# PWM_PART.net
KiCad netlist of a schematic drawn in Altium Designer
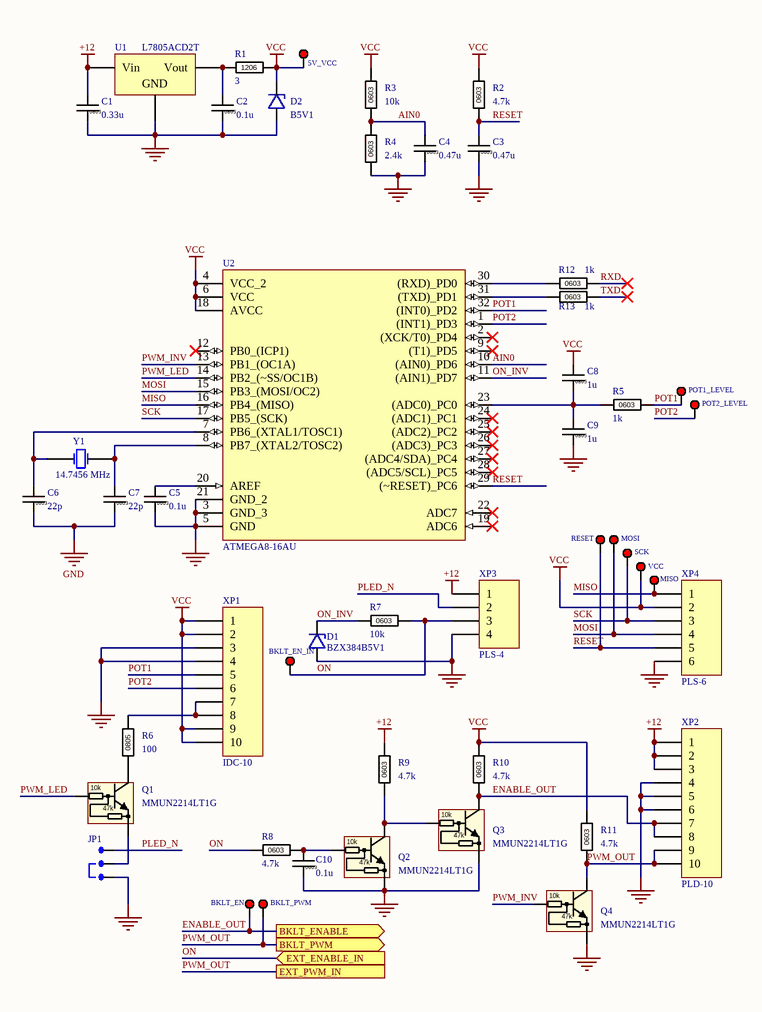
[diagram p0: PWM_PART.SchDoc]

(export (version "E")
  (design (tool "Eeschema 10.0.6"))
  (components
    (comp (ref "C1")
      (value "0805-X7R-100-0.33 мкф K")
      (footprint "CAP_0805")
      (description "Конденсатор Чип Керамический")
      (fields (field (name "VOLTAGE") "100V") (field (name "CAP") "0.33u") (field (name "FOOT") "0805"))
      (libsource (lib "main") (part "0805-X7R-100-0.33 мкф K"))
    )
    (comp (ref "C2")
      (value "0805-X7R-50-0.1 мкф K Hitano")
      (footprint "CAP_0805")
      (description "Конденсатор Чип Керамический")
      (fields (field (name "VOLTAGE") "50V") (field (name "CAP") "0.1u") (field (name "FOOT") "0805"))
      (libsource (lib "main") (part "0805-X7R-50-0.1 мкф K"))
    )
    (comp (ref "C3")
      (value "0603-X7R-50-0.47 мкф")
      (footprint "CAP_0603")
      (description "Конденсатор Чип Керамический")
      (fields (field (name "VOLTAGE") "50V") (field (name "CAP") "0.47u") (field (name "FOOT") "0603"))
      (libsource (lib "main") (part "0603-X7R-50-0.47 мкф"))
    )
    (comp (ref "C4")
      (value "0603-X7R-50-0.47 мкф")
      (footprint "CAP_0603")
      (description "Конденсатор Чип Керамический")
      (fields (field (name "VOLTAGE") "50V") (field (name "CAP") "0.47u") (field (name "FOOT") "0603"))
      (libsource (lib "main") (part "0603-X7R-50-0.47 мкф"))
    )
    (comp (ref "C5")
      (value "0603-X7R-50-0.1 мкф")
      (footprint "CAP_0603")
      (description "Конденсатор Чип Керамический")
      (fields (field (name "VOLTAGE") "50V") (field (name "CAP") "0.1u") (field (name "FOOT") "0603"))
      (libsource (lib "main") (part "0603-X7R-50-0.1 мкф"))
    )
    (comp (ref "C6")
      (value "0603-NP0-50-22 пф F")
      (footprint "CAP_0603")
      (description "Конденсатор Чип Керамический")
      (fields
        (field (name "VOLTAGE") "50V")
        (field (name "TOLERANCE") "1%")
        (field (name "CAP") "22p")
        (field (name "FOOT") "0603")
      )
      (libsource (lib "main") (part "0603-NP0-50-22 пф F"))
    )
    (comp (ref "C7")
      (value "0603-NP0-50-22 пф F")
      (footprint "CAP_0603")
      (description "Конденсатор Чип Керамический")
      (fields
        (field (name "VOLTAGE") "50V")
        (field (name "TOLERANCE") "1%")
        (field (name "CAP") "22p")
        (field (name "FOOT") "0603")
      )
      (libsource (lib "main") (part "0603-NP0-50-22 пф F"))
    )
    (comp (ref "C8")
      (value "0805-X7R-50-1 мкф")
      (footprint "CAP_0805")
      (description "Конденсатор Чип Керамический")
      (fields (field (name "VOLTAGE") "50V") (field (name "CAP") "1u") (field (name "FOOT") "0805"))
      (libsource (lib "main") (part "0805-X7R-50-1 мкф"))
    )
    (comp (ref "C9")
      (value "0805-X7R-50-1 мкф")
      (footprint "CAP_0805")
      (description "Конденсатор Чип Керамический")
      (fields (field (name "VOLTAGE") "50V") (field (name "CAP") "1u") (field (name "FOOT") "0805"))
      (libsource (lib "main") (part "0805-X7R-50-1 мкф"))
    )
    (comp (ref "C10")
      (value "0603-X7R-50-0.1 мкф")
      (footprint "CAP_0603")
      (description "Конденсатор Чип Керамический")
      (fields (field (name "VOLTAGE") "50V") (field (name "CAP") "0.1u") (field (name "FOOT") "0603"))
      (libsource (lib "main") (part "0603-X7R-50-0.1 мкф"))
    )
    (comp (ref "D1")
      (value "BZX384B5V1")
      (footprint "SOD_323 (SC-76)")
      (fields
        (field (name "HELPURL") "L:\\Dev\\Техническая документация\\Стабилитроны\\BZX384_series_Vishay.pdf")
      )
      (libsource (lib "main") (part "BZX384B5V1"))
    )
    (comp (ref "D2")
      (value "B5V1")
      (footprint "SOD_323 (SC-76)")
      (fields
        (field (name "Comment") "BZX384B5V1")
        (field (name "HELPURL") "L:\\Dev\\Техническая документация\\Стабилитроны\\BZX384_series_Vishay.pdf")
      )
      (libsource (lib "main") (part "BZX384B5V1"))
    )
    (comp (ref "JP1")
      (value "~")
      (footprint "CONN_JUMPER 3PIN 2.54MM")
      (libsource (lib "main") (part "CONN_JUMPER 2.54 MM"))
    )
    (comp (ref "Q1")
      (value "MMUN2214LT1G")
      (footprint "SOT_23")
      (description "NPN Digital Transistor")
      (fields (field (name "PUBLISHER") "Altium Limited"))
      (libsource (lib "main") (part "MMUN2214LT1G_50V 0.1A 0.25W"))
    )
    (comp (ref "Q2")
      (value "MMUN2214LT1G")
      (footprint "SOT_23")
      (description "NPN Digital Transistor")
      (fields (field (name "PUBLISHER") "Altium Limited"))
      (libsource (lib "main") (part "MMUN2214LT1G_50V 0.1A 0.25W"))
    )
    (comp (ref "Q3")
      (value "MMUN2214LT1G")
      (footprint "SOT_23")
      (description "NPN Digital Transistor")
      (fields (field (name "PUBLISHER") "Altium Limited"))
      (libsource (lib "main") (part "MMUN2214LT1G_50V 0.1A 0.25W"))
    )
    (comp (ref "Q4")
      (value "MMUN2214LT1G")
      (footprint "SOT_23")
      (description "NPN Digital Transistor")
      (fields (field (name "PUBLISHER") "Altium Limited"))
      (libsource (lib "main") (part "MMUN2214LT1G_50V 0.1A 0.25W"))
    )
    (comp (ref "R1")
      (value "3")
      (footprint "resistor_1206")
      (description "Резистор Чип")
      (fields (field (name "POWER") "0.25W") (field (name "FOOT") "1206") (field (name "Comment") "1206-3 J"))
      (libsource (lib "main") (part "1206-3 J"))
    )
    (comp (ref "R2")
      (value "4.7k")
      (footprint "resistor_0603")
      (description "Резистор Чип")
      (fields
        (field (name "POWER") "0.1W")
        (field (name "FOOT") "0603")
        (field (name "Comment") "0603-4.7 к J")
      )
      (libsource (lib "main") (part "0603-4.7 к J"))
    )
    (comp (ref "R3")
      (value "10k")
      (footprint "resistor_0603")
      (description "Резистор Чип")
      (fields
        (field (name "POWER") "0.1W")
        (field (name "FOOT") "0603")
        (field (name "Comment") "0603-10к J")
      )
      (libsource (lib "main") (part "0603-10 к J"))
    )
    (comp (ref "R4")
      (value "2.4k")
      (footprint "resistor_0603")
      (description "Резистор Чип")
      (fields (field (name "POWER") "0.1W") (field (name "TOLERANCE") "1%") (field (name "FOOT") "0603"))
      (libsource (lib "main") (part "0603-2.49 к F"))
    )
    (comp (ref "R5")
      (value "1k")
      (footprint "RESistor_0603")
      (description "Резистор Чип")
      (fields
        (field (name "POWER") "0.1W")
        (field (name "FOOT") "0603")
        (field (name "Comment") "0603-1 к J")
      )
      (libsource (lib "main") (part "0603-1 к J"))
    )
    (comp (ref "R6")
      (value "100")
      (footprint "resistor_0805")
      (description "Резистор Чип")
      (fields
        (field (name "POWER") "0.125W")
        (field (name "FOOT") "0805")
        (field (name "Comment") "0805-100 J")
      )
      (libsource (lib "main") (part "0805-100 J"))
    )
    (comp (ref "R7")
      (value "10k")
      (footprint "resistor_0603")
      (description "Резистор Чип")
      (fields
        (field (name "POWER") "0.1W")
        (field (name "FOOT") "0603")
        (field (name "Comment") "0603-10к J")
      )
      (libsource (lib "main") (part "0603-10 к J"))
    )
    (comp (ref "R8")
      (value "4.7k")
      (footprint "resistor_0603")
      (description "Резистор Чип")
      (fields
        (field (name "POWER") "0.1W")
        (field (name "FOOT") "0603")
        (field (name "Comment") "0603-4.7 к J")
      )
      (libsource (lib "main") (part "0603-4.7 к J"))
    )
    (comp (ref "R9")
      (value "4.7k")
      (footprint "resistor_0603")
      (description "Резистор Чип")
      (fields
        (field (name "POWER") "0.1W")
        (field (name "FOOT") "0603")
        (field (name "Comment") "0603-4.7 к J")
      )
      (libsource (lib "main") (part "0603-4.7 к J"))
    )
    (comp (ref "R10")
      (value "4.7k")
      (footprint "resistor_0603")
      (description "Резистор Чип")
      (fields
        (field (name "POWER") "0.1W")
        (field (name "FOOT") "0603")
        (field (name "Comment") "0603-4.7 к J")
      )
      (libsource (lib "main") (part "0603-4.7 к J"))
    )
    (comp (ref "R11")
      (value "4.7k")
      (footprint "resistor_0603")
      (description "Резистор Чип")
      (fields
        (field (name "POWER") "0.1W")
        (field (name "FOOT") "0603")
        (field (name "Comment") "0603-4.7 к J")
      )
      (libsource (lib "main") (part "0603-4.7 к J"))
    )
    (comp (ref "R12")
      (value "1k")
      (footprint "RESistor_0603")
      (description "Резистор Чип")
      (fields
        (field (name "POWER") "0.1W")
        (field (name "FOOT") "0603")
        (field (name "Comment") "0603-1 к J")
      )
      (libsource (lib "main") (part "0603-1 к J"))
    )
    (comp (ref "R13")
      (value "1k")
      (footprint "RESistor_0603")
      (description "Резистор Чип")
      (fields
        (field (name "POWER") "0.1W")
        (field (name "FOOT") "0603")
        (field (name "Comment") "0603-1 к J")
      )
      (libsource (lib "main") (part "0603-1 к J"))
    )
    (comp (ref "TP1")
      (value "5V_VCC")
      (footprint "OTHER_SMD_TP_1.5MM")
      (libsource (lib "main") (part "Test Point_1.5MM"))
    )
    (comp (ref "TP2")
      (value "MISO")
      (footprint "OTHER_SMD_TP_1.5MM")
      (libsource (lib "main") (part "Test Point_1.5MM"))
    )
    (comp (ref "TP3")
      (value "VCC")
      (footprint "OTHER_SMD_TP_1.5MM")
      (libsource (lib "main") (part "Test Point_1.5MM"))
    )
    (comp (ref "TP4")
      (value "SCK")
      (footprint "OTHER_SMD_TP_1.5MM")
      (libsource (lib "main") (part "Test Point_1.5MM"))
    )
    (comp (ref "TP5")
      (value "MOSI")
      (footprint "OTHER_SMD_TP_1.5MM")
      (libsource (lib "main") (part "Test Point_1.5MM"))
    )
    (comp (ref "TP6")
      (value "RESET")
      (footprint "OTHER_SMD_TP_1.5MM")
      (libsource (lib "main") (part "Test Point_1.5MM"))
    )
    (comp (ref "TP7")
      (value "BKLT_EN")
      (footprint "OTHER_SMD_TP_1.5MM")
      (libsource (lib "main") (part "Test Point_1.5MM"))
    )
    (comp (ref "TP8")
      (value "BKLT_PWM")
      (footprint "OTHER_SMD_TP_1.5MM")
      (libsource (lib "main") (part "Test Point_1.5MM"))
    )
    (comp (ref "TP9")
      (value "BKLT_EN_IN")
      (footprint "OTHER_SMD_TP_1.5MM")
      (libsource (lib "main") (part "Test Point_1.5MM"))
    )
    (comp (ref "TP10")
      (value "POT1_LEVEL")
      (footprint "OTHER_SMD_TP_1.5MM")
      (libsource (lib "main") (part "Test Point_1.5MM"))
    )
    (comp (ref "TP11")
      (value "POT2_LEVEL")
      (footprint "OTHER_SMD_TP_1.5MM")
      (libsource (lib "main") (part "Test Point_1.5MM"))
    )
    (comp (ref "U1")
      (value "L7805ACD2T")
      (footprint "D2-PAK")
      (description "Стабилизатор напряжения +5В 1.5А, [D2-PAK]")
      (fields (field (name "PUBLISHER") "Altium Limited"))
      (libsource (lib "main") (part "LDO_L7805ACD2T-TR"))
    )
    (comp (ref "U2")
      (value "ATMEGA8-16AU")
      (footprint "TQFP_32")
      (description "AVR AVRÂ® ATmega Microcontroller IC 8-Bit 16MHz 8KB _4K x 16_ FLASH 32-TQFP _7x7_")
      (fields (field (name "MF") "Microchip Technology"))
      (libsource (lib "main") (part "MCU_ATMEGA8-16AU"))
    )
    (comp (ref "XP1")
      (value "IDC-10")
      (footprint "CONN_IDC-10")
      (description "Header, 10-Pin")
      (fields (field (name "PUBLISHER") "Altium Limited"))
      (libsource (lib "main") (part "CONN_IDC-10 (Single Row)"))
    )
    (comp (ref "XP2")
      (value "PLD-10")
      (footprint "CONN_PLD-10")
      (description "Header, 10-Pin")
      (fields (field (name "PUBLISHER") "Altium Limited"))
      (libsource (lib "main") (part "CONN_Header 10 (Single Row)_1"))
    )
    (comp (ref "XP3")
      (value "PLS-4")
      (footprint "CONN_PLS-4")
      (description "Header, 4-Pin")
      (fields (field (name "PUBLISHER") "Altium Limited"))
      (libsource (lib "main") (part "CONN_PLS-4"))
    )
    (comp (ref "XP4")
      (value "PLS-6")
      (footprint "CONN_PLD-6")
      (description "Header, 6-Pin")
      (fields (field (name "PUBLISHER") "Altium Limited"))
      (libsource (lib "main") (part "CONN_PLS-6"))
    )
    (comp (ref "Y1")
      (value "14.7456 MHz")
      (footprint "CRYSTAL_HC-49S")
      (description "14.7456 МГц имп. HC-49SM, Кварцевый резонатор")
      (fields (field (name "PUBLISHER") "Altium Limited"))
      (libsource (lib "main") (part "CRYSTAL_14.7456 MHz"))
    )
  )
  (nets
    (net (code "1") (name "+12") (class "Default")
      (node (ref "C1") (pin "1") (pinfunction "1_1") (pintype "passive"))
      (node (ref "R9") (pin "2") (pinfunction "2_2") (pintype "passive"))
      (node (ref "U1") (pin "1") (pinfunction "Vin_1") (pintype "passive"))
      (node (ref "XP2") (pin "1") (pinfunction "1_1") (pintype "passive"))
      (node (ref "XP2") (pin "2") (pinfunction "2_2") (pintype "passive"))
      (node (ref "XP2") (pin "3") (pinfunction "3_3") (pintype "passive"))
      (node (ref "XP3") (pin "1") (pinfunction "1_1") (pintype "passive"))
    )
    (net (code "2") (name "/AIN0") (class "Default")
      (node (ref "C4") (pin "1") (pinfunction "1_1") (pintype "passive"))
      (node (ref "R3") (pin "1") (pinfunction "1_1") (pintype "passive"))
      (node (ref "R4") (pin "2") (pinfunction "2_2") (pintype "passive"))
      (node (ref "U2") (pin "10") (pinfunction "(AIN0)_PD6_10") (pintype "bidirectional"))
    )
    (net (code "3") (name "/ENABLE_OUT") (class "Default")
      (node (ref "Q3") (pin "3") (pinfunction "C_3") (pintype "passive"))
      (node (ref "R10") (pin "1") (pinfunction "1_1") (pintype "passive"))
      (node (ref "TP7") (pin "1") (pinfunction "1_1") (pintype "passive"))
      (node (ref "XP2") (pin "7") (pinfunction "7_7") (pintype "passive"))
      (node (ref "XP2") (pin "8") (pinfunction "8_8") (pintype "passive"))
    )
    (net (code "4") (name "/MISO") (class "Default")
      (node (ref "TP2") (pin "1") (pinfunction "1_1") (pintype "passive"))
      (node (ref "U2") (pin "16") (pinfunction "PB4_(MISO)_16") (pintype "bidirectional"))
      (node (ref "XP4") (pin "1") (pinfunction "1_1") (pintype "passive"))
    )
    (net (code "5") (name "/MOSI") (class "Default")
      (node (ref "TP5") (pin "1") (pinfunction "1_1") (pintype "passive"))
      (node (ref "U2") (pin "15") (pinfunction "PB3_(MOSI/OC2)_15") (pintype "bidirectional"))
      (node (ref "XP4") (pin "4") (pinfunction "4_4") (pintype "passive"))
    )
    (net (code "6") (name "/ON") (class "Default")
      (node (ref "R7") (pin "2") (pinfunction "2_2") (pintype "passive"))
      (node (ref "R8") (pin "1") (pinfunction "1_1") (pintype "passive"))
      (node (ref "TP9") (pin "1") (pinfunction "1_1") (pintype "passive"))
      (node (ref "XP3") (pin "3") (pinfunction "3_3") (pintype "passive"))
    )
    (net (code "7") (name "/ON_INV") (class "Default")
      (node (ref "D1") (pin "C") (pinfunction "2_C") (pintype "passive"))
      (node (ref "R7") (pin "1") (pinfunction "1_1") (pintype "passive"))
      (node (ref "U2") (pin "11") (pinfunction "(AIN1)_PD7_11") (pintype "bidirectional"))
    )
    (net (code "8") (name "/PLED_N") (class "Default")
      (node (ref "JP1") (pin "3") (pinfunction "3_3") (pintype "passive"))
      (node (ref "XP3") (pin "2") (pinfunction "2_2") (pintype "passive"))
    )
    (net (code "9") (name "/POT1") (class "Default")
      (node (ref "R5") (pin "2") (pinfunction "2_2") (pintype "passive"))
      (node (ref "TP10") (pin "1") (pinfunction "1_1") (pintype "passive"))
      (node (ref "U2") (pin "32") (pinfunction "(INT0)_PD2_32") (pintype "bidirectional"))
      (node (ref "XP1") (pin "5") (pinfunction "5_5") (pintype "passive"))
    )
    (net (code "10") (name "/POT2") (class "Default")
      (node (ref "TP11") (pin "1") (pinfunction "1_1") (pintype "passive"))
      (node (ref "U2") (pin "1") (pinfunction "(INT1)_PD3_1") (pintype "bidirectional"))
      (node (ref "XP1") (pin "6") (pinfunction "6_6") (pintype "passive"))
    )
    (net (code "11") (name "/PWM_INV") (class "Default")
      (node (ref "Q4") (pin "1") (pinfunction "B_1") (pintype "passive"))
      (node (ref "U2") (pin "13") (pinfunction "PB1_(OC1A)_13") (pintype "bidirectional"))
    )
    (net (code "12") (name "/PWM_LED") (class "Default")
      (node (ref "Q1") (pin "1") (pinfunction "B_1") (pintype "passive"))
      (node (ref "U2") (pin "14") (pinfunction "PB2_(~SS/OC1B)_14") (pintype "bidirectional"))
    )
    (net (code "13") (name "/PWM_OUT") (class "Default")
      (node (ref "Q4") (pin "3") (pinfunction "C_3") (pintype "passive"))
      (node (ref "R11") (pin "1") (pinfunction "1_1") (pintype "passive"))
      (node (ref "TP8") (pin "1") (pinfunction "1_1") (pintype "passive"))
      (node (ref "XP2") (pin "10") (pinfunction "10_10") (pintype "passive"))
      (node (ref "XP2") (pin "9") (pinfunction "9_9") (pintype "passive"))
    )
    (net (code "14") (name "/RESET") (class "Default")
      (node (ref "C3") (pin "1") (pinfunction "1_1") (pintype "passive"))
      (node (ref "R2") (pin "1") (pinfunction "1_1") (pintype "passive"))
      (node (ref "TP6") (pin "1") (pinfunction "1_1") (pintype "passive"))
      (node (ref "U2") (pin "29") (pinfunction "(~RESET)_PC6_29") (pintype "bidirectional"))
      (node (ref "XP4") (pin "5") (pinfunction "5_5") (pintype "passive"))
    )
    (net (code "15") (name "/RXD") (class "Default")
      (node (ref "R12") (pin "2") (pinfunction "2_2") (pintype "passive+no_connect"))
    )
    (net (code "16") (name "/SCK") (class "Default")
      (node (ref "TP4") (pin "1") (pinfunction "1_1") (pintype "passive"))
      (node (ref "U2") (pin "17") (pinfunction "PB5_(SCK)_17") (pintype "bidirectional"))
      (node (ref "XP4") (pin "3") (pinfunction "3_3") (pintype "passive"))
    )
    (net (code "17") (name "/TXD") (class "Default")
      (node (ref "R13") (pin "2") (pinfunction "2_2") (pintype "passive+no_connect"))
    )
    (net (code "18") (name "GND") (class "Default")
      (node (ref "C1") (pin "2") (pinfunction "2_2") (pintype "passive"))
      (node (ref "C10") (pin "2") (pinfunction "2_2") (pintype "passive"))
      (node (ref "C2") (pin "2") (pinfunction "2_2") (pintype "passive"))
      (node (ref "C3") (pin "2") (pinfunction "2_2") (pintype "passive"))
      (node (ref "C4") (pin "2") (pinfunction "2_2") (pintype "passive"))
      (node (ref "C5") (pin "2") (pinfunction "2_2") (pintype "passive"))
      (node (ref "C6") (pin "2") (pinfunction "2_2") (pintype "passive"))
      (node (ref "C7") (pin "2") (pinfunction "2_2") (pintype "passive"))
      (node (ref "C9") (pin "2") (pinfunction "2_2") (pintype "passive"))
      (node (ref "D1") (pin "A") (pinfunction "1_A") (pintype "passive"))
      (node (ref "D2") (pin "A") (pinfunction "1_A") (pintype "passive"))
      (node (ref "JP1") (pin "1") (pinfunction "1_1") (pintype "passive"))
      (node (ref "Q2") (pin "2") (pinfunction "E_2") (pintype "passive"))
      (node (ref "Q3") (pin "2") (pinfunction "E_2") (pintype "passive"))
      (node (ref "Q4") (pin "2") (pinfunction "E_2") (pintype "passive"))
      (node (ref "R4") (pin "1") (pinfunction "1_1") (pintype "passive"))
      (node (ref "U1") (pin "2") (pinfunction "GND_2") (pintype "passive"))
      (node (ref "U2") (pin "21") (pinfunction "GND_2_21") (pintype "passive"))
      (node (ref "U2") (pin "3") (pinfunction "GND_3_3") (pintype "passive"))
      (node (ref "U2") (pin "5") (pinfunction "GND_5") (pintype "passive"))
      (node (ref "XP1") (pin "3") (pinfunction "3_3") (pintype "passive"))
      (node (ref "XP1") (pin "4") (pinfunction "4_4") (pintype "passive"))
      (node (ref "XP2") (pin "4") (pinfunction "4_4") (pintype "passive"))
      (node (ref "XP2") (pin "5") (pinfunction "5_5") (pintype "passive"))
      (node (ref "XP2") (pin "6") (pinfunction "6_6") (pintype "passive"))
      (node (ref "XP3") (pin "4") (pinfunction "4_4") (pintype "passive"))
      (node (ref "XP4") (pin "6") (pinfunction "6_6") (pintype "passive"))
    )
    (net (code "19") (name "Net-(Q1-C)") (class "Default")
      (node (ref "Q1") (pin "3") (pinfunction "C_3") (pintype "passive"))
      (node (ref "R6") (pin "1") (pinfunction "1_1") (pintype "passive"))
    )
    (net (code "20") (name "Net-(Q1-E)") (class "Default")
      (node (ref "JP1") (pin "2") (pinfunction "2_2") (pintype "passive"))
      (node (ref "Q1") (pin "2") (pinfunction "E_2") (pintype "passive"))
    )
    (net (code "21") (name "Net-(Q2-B)") (class "Default")
      (node (ref "C10") (pin "1") (pinfunction "1_1") (pintype "passive"))
      (node (ref "Q2") (pin "1") (pinfunction "B_1") (pintype "passive"))
      (node (ref "R8") (pin "2") (pinfunction "2_2") (pintype "passive"))
    )
    (net (code "22") (name "Net-(Q2-C)") (class "Default")
      (node (ref "Q2") (pin "3") (pinfunction "C_3") (pintype "passive"))
      (node (ref "Q3") (pin "1") (pinfunction "B_1") (pintype "passive"))
      (node (ref "R9") (pin "1") (pinfunction "1_1") (pintype "passive"))
    )
    (net (code "23") (name "Net-(R6-Pad2)") (class "Default")
      (node (ref "R6") (pin "2") (pinfunction "2_2") (pintype "passive"))
      (node (ref "XP1") (pin "7") (pinfunction "7_7") (pintype "passive"))
      (node (ref "XP1") (pin "8") (pinfunction "8_8") (pintype "passive"))
    )
    (net (code "24") (name "Net-(U1-Vout)") (class "Default")
      (node (ref "C2") (pin "1") (pinfunction "1_1") (pintype "passive"))
      (node (ref "R1") (pin "1") (pinfunction "1_1") (pintype "passive"))
      (node (ref "U1") (pin "3") (pinfunction "Vout_3") (pintype "passive"))
    )
    (net (code "25") (name "Net-(U2-(ADC0)_PC0)") (class "Default")
      (node (ref "C8") (pin "2") (pinfunction "2_2") (pintype "passive"))
      (node (ref "C9") (pin "1") (pinfunction "1_1") (pintype "passive"))
      (node (ref "R5") (pin "1") (pinfunction "1_1") (pintype "passive"))
      (node (ref "U2") (pin "23") (pinfunction "(ADC0)_PC0_23") (pintype "bidirectional"))
    )
    (net (code "26") (name "Net-(U2-(RXD)_PD0)") (class "Default")
      (node (ref "R12") (pin "1") (pinfunction "1_1") (pintype "passive"))
      (node (ref "U2") (pin "30") (pinfunction "(RXD)_PD0_30") (pintype "bidirectional"))
    )
    (net (code "27") (name "Net-(U2-(TXD)_PD1)") (class "Default")
      (node (ref "R13") (pin "1") (pinfunction "1_1") (pintype "passive"))
      (node (ref "U2") (pin "31") (pinfunction "(TXD)_PD1_31") (pintype "bidirectional"))
    )
    (net (code "28") (name "Net-(U2-AREF)") (class "Default")
      (node (ref "C5") (pin "1") (pinfunction "1_1") (pintype "passive"))
      (node (ref "U2") (pin "20") (pinfunction "AREF_20") (pintype "input"))
    )
    (net (code "29") (name "Net-(U2-PB6_(XTAL1{slash}TOSC1))") (class "Default")
      (node (ref "C6") (pin "1") (pinfunction "1_1") (pintype "passive"))
      (node (ref "U2") (pin "7") (pinfunction "PB6_(XTAL1/TOSC1)_7") (pintype "bidirectional"))
      (node (ref "Y1") (pin "1") (pinfunction "OSC1_1") (pintype "passive"))
    )
    (net (code "30") (name "Net-(U2-PB7_(XTAL2{slash}TOSC2))") (class "Default")
      (node (ref "C7") (pin "1") (pinfunction "1_1") (pintype "passive"))
      (node (ref "U2") (pin "8") (pinfunction "PB7_(XTAL2/TOSC2)_8") (pintype "bidirectional"))
      (node (ref "Y1") (pin "2") (pinfunction "OSC2_2") (pintype "passive"))
    )
    (net (code "31") (name "VCC") (class "Default")
      (node (ref "C8") (pin "1") (pinfunction "1_1") (pintype "passive"))
      (node (ref "D2") (pin "C") (pinfunction "2_C") (pintype "passive"))
      (node (ref "R1") (pin "2") (pinfunction "2_2") (pintype "passive"))
      (node (ref "R10") (pin "2") (pinfunction "2_2") (pintype "passive"))
      (node (ref "R11") (pin "2") (pinfunction "2_2") (pintype "passive"))
      (node (ref "R2") (pin "2") (pinfunction "2_2") (pintype "passive"))
      (node (ref "R3") (pin "2") (pinfunction "2_2") (pintype "passive"))
      (node (ref "TP1") (pin "1") (pinfunction "1_1") (pintype "passive"))
      (node (ref "TP3") (pin "1") (pinfunction "1_1") (pintype "passive"))
      (node (ref "U2") (pin "18") (pinfunction "AVCC_18") (pintype "power_in"))
      (node (ref "U2") (pin "4") (pinfunction "VCC_2_4") (pintype "power_in"))
      (node (ref "U2") (pin "6") (pinfunction "VCC_6") (pintype "power_in"))
      (node (ref "XP1") (pin "1") (pinfunction "1_1") (pintype "passive"))
      (node (ref "XP1") (pin "10") (pinfunction "10_10") (pintype "passive"))
      (node (ref "XP1") (pin "2") (pinfunction "2_2") (pintype "passive"))
      (node (ref "XP1") (pin "9") (pinfunction "9_9") (pintype "passive"))
      (node (ref "XP4") (pin "2") (pinfunction "2_2") (pintype "passive"))
    )
    (net (code "32") (name "unconnected-(U2-(ADC1)_PC1-Pad24)") (class "Default")
      (node (ref "U2") (pin "24") (pinfunction "(ADC1)_PC1_24") (pintype "bidirectional+no_connect"))
    )
    (net (code "33") (name "unconnected-(U2-(ADC2)_PC2-Pad25)") (class "Default")
      (node (ref "U2") (pin "25") (pinfunction "(ADC2)_PC2_25") (pintype "bidirectional+no_connect"))
    )
    (net (code "34") (name "unconnected-(U2-(ADC3)_PC3-Pad26)") (class "Default")
      (node (ref "U2") (pin "26") (pinfunction "(ADC3)_PC3_26") (pintype "bidirectional+no_connect"))
    )
    (net (code "35") (name "unconnected-(U2-(ADC4{slash}SDA)_PC4-Pad27)") (class "Default")
      (node (ref "U2") (pin "27") (pinfunction "(ADC4/SDA)_PC4_27") (pintype "bidirectional+no_connect"))
    )
    (net (code "36") (name "unconnected-(U2-(ADC5{slash}SCL)_PC5-Pad28)") (class "Default")
      (node (ref "U2") (pin "28") (pinfunction "(ADC5/SCL)_PC5_28") (pintype "bidirectional+no_connect"))
    )
    (net (code "37") (name "unconnected-(U2-(T1)_PD5-Pad9)") (class "Default")
      (node (ref "U2") (pin "9") (pinfunction "(T1)_PD5_9") (pintype "bidirectional+no_connect"))
    )
    (net (code "38") (name "unconnected-(U2-(XCK{slash}T0)_PD4-Pad2)") (class "Default")
      (node (ref "U2") (pin "2") (pinfunction "(XCK/T0)_PD4_2") (pintype "bidirectional+no_connect"))
    )
    (net (code "39") (name "unconnected-(U2-ADC6-Pad19)") (class "Default")
      (node (ref "U2") (pin "19") (pinfunction "ADC6_19") (pintype "input+no_connect"))
    )
    (net (code "40") (name "unconnected-(U2-ADC7-Pad22)") (class "Default")
      (node (ref "U2") (pin "22") (pinfunction "ADC7_22") (pintype "input+no_connect"))
    )
    (net (code "41") (name "unconnected-(U2-PB0_(ICP1)-Pad12)") (class "Default")
      (node (ref "U2") (pin "12") (pinfunction "PB0_(ICP1)_12") (pintype "bidirectional+no_connect"))
    )
  )
)
